# Microcontroller_and_Memory.net
KiCad netlist of a schematic drawn in Altium Designer
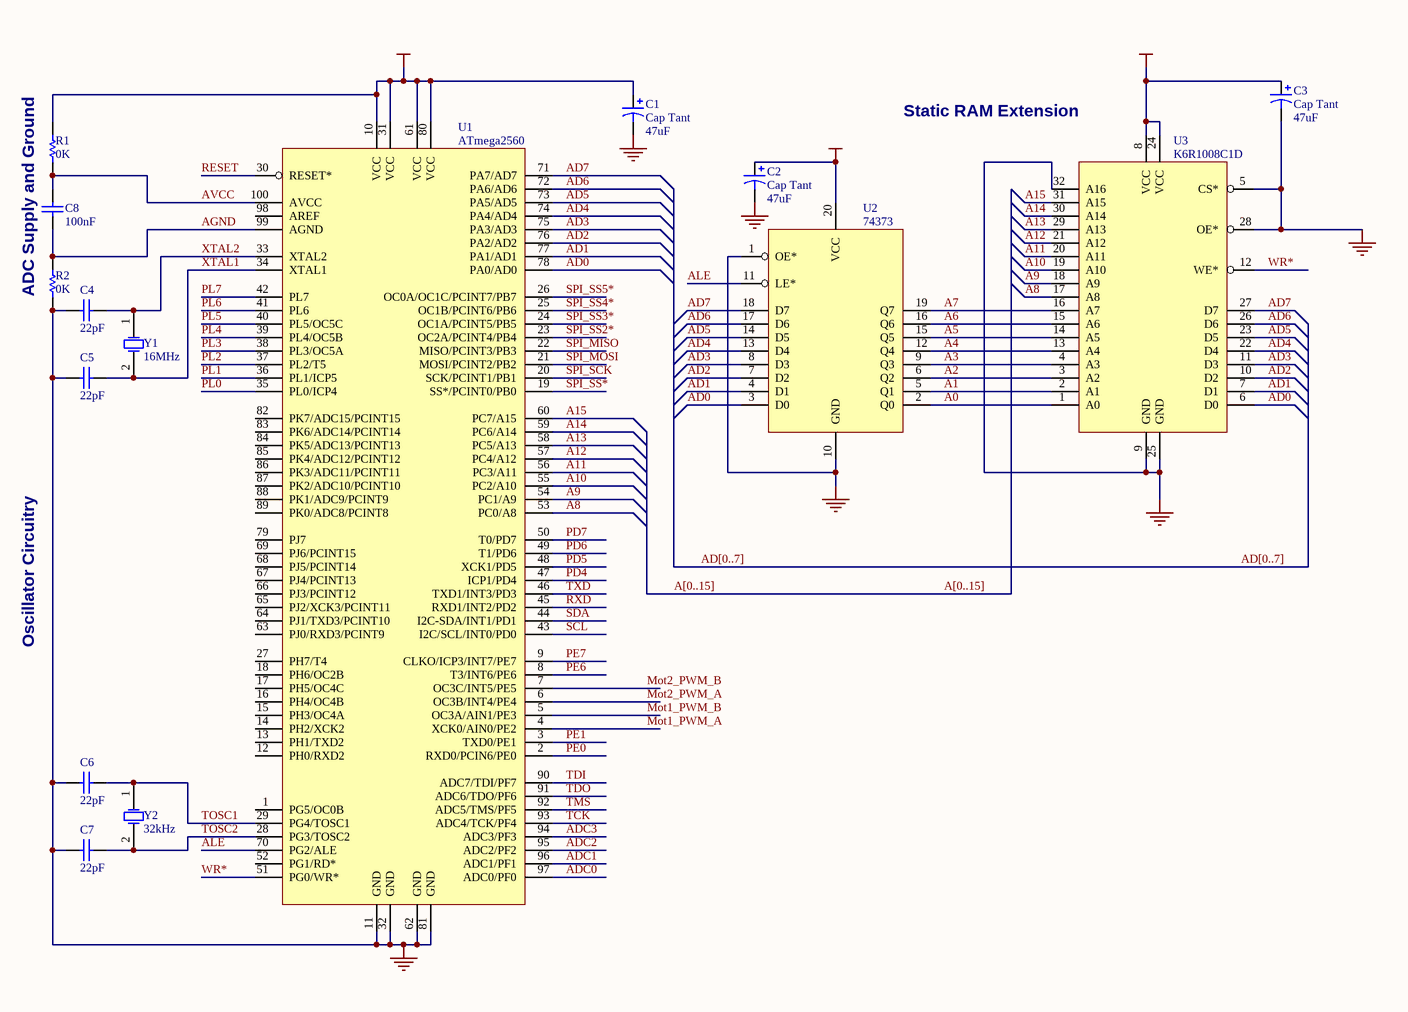
[diagram p0: Microcontroller and Memory.SCHDOC]

(export (version "E")
  (design (tool "Eeschema 10.0.6"))
  (components
    (comp (ref "C1")
      (value "Cap Tant")
      (footprint "CAPR5-4X5")
      (description "Polarized Capacitor (Axial)")
      (fields (field (name "ALTIUM_VALUE") "47uF") (field (name "PUBLISHER") "Altium Limited"))
      (libsource (lib "Miscellaneous Devices") (part "Cap Pol2"))
    )
    (comp (ref "C2")
      (value "Cap Tant")
      (footprint "CAPR5-4X5")
      (description "Polarized Capacitor (Axial)")
      (fields (field (name "ALTIUM_VALUE") "47uF") (field (name "PUBLISHER") "Altium Limited"))
      (libsource (lib "Miscellaneous Devices") (part "Cap Pol2"))
    )
    (comp (ref "C3")
      (value "Cap Tant")
      (footprint "CAPR5-4X5")
      (description "Polarized Capacitor (Axial)")
      (fields (field (name "ALTIUM_VALUE") "47uF") (field (name "PUBLISHER") "Altium Limited"))
      (libsource (lib "Miscellaneous Devices") (part "Cap Pol2"))
    )
    (comp (ref "C4")
      (value "22pF")
      (footprint "BCY-W2/D3.1")
      (description "Capacitor")
      (fields (field (name "PUBLISHER") "Altium Limited"))
      (libsource (lib "Miscellaneous Devices") (part "Cap"))
    )
    (comp (ref "C5")
      (value "22pF")
      (footprint "BCY-W2/D3.1")
      (description "Capacitor")
      (fields (field (name "PUBLISHER") "Altium Limited"))
      (libsource (lib "Miscellaneous Devices") (part "Cap"))
    )
    (comp (ref "C6")
      (value "22pF")
      (footprint "BCY-W2/D3.1")
      (description "Capacitor")
      (fields (field (name "PUBLISHER") "Altium Limited"))
      (libsource (lib "Miscellaneous Devices") (part "Cap"))
    )
    (comp (ref "C7")
      (value "22pF")
      (footprint "BCY-W2/D3.1")
      (description "Capacitor")
      (fields (field (name "PUBLISHER") "Altium Limited"))
      (libsource (lib "Miscellaneous Devices") (part "Cap"))
    )
    (comp (ref "C8")
      (value "100nF")
      (footprint "BCY-W2/D3.1")
      (description "Capacitor")
      (fields (field (name "PUBLISHER") "Altium Limited"))
      (libsource (lib "Miscellaneous Devices") (part "Cap"))
    )
    (comp (ref "R1")
      (value "0K")
      (footprint "AXIAL-0.3")
      (description "Resistor")
      (fields (field (name "PUBLISHER") "Altium Limited"))
      (libsource (lib "Miscellaneous Devices") (part "Res1"))
    )
    (comp (ref "R2")
      (value "0K")
      (footprint "AXIAL-0.3")
      (description "Resistor")
      (fields (field (name "PUBLISHER") "Altium Limited"))
      (libsource (lib "Miscellaneous Devices") (part "Res1"))
    )
    (comp (ref "U1")
      (value "ATmega2560")
      (footprint "Sumo:F-QFP14X14-G100/Z17N")
      (description "Atmel ATmega2560 MCU")
      (libsource (lib "Schematic Library") (part "ATmega2560"))
    )
    (comp (ref "U2")
      (value "74373")
      (footprint "SO-G20/Y1.45")
      (description "Octal 8-bit D-type Latch")
      (libsource (lib "Schematic Library") (part "74373"))
    )
    (comp (ref "U3")
      (value "K6R1008C1D")
      (footprint "SO-G32/Y1.45")
      (description "Samsung 128Kx8 High-Speed Static RAM")
      (libsource (lib "Schematic Library") (part "K6R1008C1D"))
    )
    (comp (ref "Y1")
      (value "16MHz")
      (footprint "BCY-W2/D3.1")
      (description "Crystal Oscillator")
      (fields (field (name "PUBLISHER") "Altium Limited"))
      (libsource (lib "Miscellaneous Devices") (part "XTAL"))
    )
    (comp (ref "Y2")
      (value "32kHz")
      (footprint "BCY-W2/D3.1")
      (description "Crystal Oscillator")
      (fields (field (name "PUBLISHER") "Altium Limited"))
      (libsource (lib "Miscellaneous Devices") (part "XTAL"))
    )
  )
  (nets
    (net (code "1") (name "/A0") (class "Default")
      (node (ref "U2") (pin "2") (pinfunction "Q0_2") (pintype "passive"))
      (node (ref "U3") (pin "1") (pinfunction "A0_1") (pintype "passive"))
    )
    (net (code "2") (name "/A1") (class "Default")
      (node (ref "U2") (pin "5") (pinfunction "Q1_5") (pintype "passive"))
      (node (ref "U3") (pin "2") (pinfunction "A1_2") (pintype "passive"))
    )
    (net (code "3") (name "/A2") (class "Default")
      (node (ref "U2") (pin "6") (pinfunction "Q2_6") (pintype "passive"))
      (node (ref "U3") (pin "3") (pinfunction "A2_3") (pintype "passive"))
    )
    (net (code "4") (name "/A3") (class "Default")
      (node (ref "U2") (pin "9") (pinfunction "Q3_9") (pintype "passive"))
      (node (ref "U3") (pin "4") (pinfunction "A3_4") (pintype "passive"))
    )
    (net (code "5") (name "/A4") (class "Default")
      (node (ref "U2") (pin "12") (pinfunction "Q4_12") (pintype "passive"))
      (node (ref "U3") (pin "13") (pinfunction "A4_13") (pintype "passive"))
    )
    (net (code "6") (name "/A5") (class "Default")
      (node (ref "U2") (pin "15") (pinfunction "Q5_15") (pintype "passive"))
      (node (ref "U3") (pin "14") (pinfunction "A5_14") (pintype "passive"))
    )
    (net (code "7") (name "/A6") (class "Default")
      (node (ref "U2") (pin "16") (pinfunction "Q6_16") (pintype "passive"))
      (node (ref "U3") (pin "15") (pinfunction "A6_15") (pintype "passive"))
    )
    (net (code "8") (name "/A7") (class "Default")
      (node (ref "U2") (pin "19") (pinfunction "Q7_19") (pintype "passive"))
      (node (ref "U3") (pin "16") (pinfunction "A7_16") (pintype "passive"))
    )
    (net (code "9") (name "/A8") (class "Default")
      (node (ref "U1") (pin "53") (pinfunction "PC0/A8_53") (pintype "passive"))
      (node (ref "U3") (pin "17") (pinfunction "A8_17") (pintype "passive"))
    )
    (net (code "10") (name "/A9") (class "Default")
      (node (ref "U1") (pin "54") (pinfunction "PC1/A9_54") (pintype "passive"))
      (node (ref "U3") (pin "18") (pinfunction "A9_18") (pintype "passive"))
    )
    (net (code "11") (name "/A10") (class "Default")
      (node (ref "U1") (pin "55") (pinfunction "PC2/A10_55") (pintype "passive"))
      (node (ref "U3") (pin "19") (pinfunction "A10_19") (pintype "passive"))
    )
    (net (code "12") (name "/A11") (class "Default")
      (node (ref "U1") (pin "56") (pinfunction "PC3/A11_56") (pintype "passive"))
      (node (ref "U3") (pin "20") (pinfunction "A11_20") (pintype "passive"))
    )
    (net (code "13") (name "/A12") (class "Default")
      (node (ref "U1") (pin "57") (pinfunction "PC4/A12_57") (pintype "passive"))
      (node (ref "U3") (pin "21") (pinfunction "A12_21") (pintype "passive"))
    )
    (net (code "14") (name "/A13") (class "Default")
      (node (ref "U1") (pin "58") (pinfunction "PC5/A13_58") (pintype "passive"))
      (node (ref "U3") (pin "29") (pinfunction "A13_29") (pintype "passive"))
    )
    (net (code "15") (name "/A14") (class "Default")
      (node (ref "U1") (pin "59") (pinfunction "PC6/A14_59") (pintype "passive"))
      (node (ref "U3") (pin "30") (pinfunction "A14_30") (pintype "passive"))
    )
    (net (code "16") (name "/A15") (class "Default")
      (node (ref "U1") (pin "60") (pinfunction "PC7/A15_60") (pintype "passive"))
      (node (ref "U3") (pin "31") (pinfunction "A15_31") (pintype "passive"))
    )
    (net (code "17") (name "/AD0") (class "Default")
      (node (ref "U1") (pin "78") (pinfunction "PA0/AD0_78") (pintype "passive"))
      (node (ref "U2") (pin "3") (pinfunction "D0_3") (pintype "passive"))
      (node (ref "U3") (pin "6") (pinfunction "D0_6") (pintype "passive"))
    )
    (net (code "18") (name "/AD1") (class "Default")
      (node (ref "U1") (pin "77") (pinfunction "PA1/AD1_77") (pintype "passive"))
      (node (ref "U2") (pin "4") (pinfunction "D1_4") (pintype "passive"))
      (node (ref "U3") (pin "7") (pinfunction "D1_7") (pintype "passive"))
    )
    (net (code "19") (name "/AD2") (class "Default")
      (node (ref "U1") (pin "76") (pinfunction "PA2/AD2_76") (pintype "passive"))
      (node (ref "U2") (pin "7") (pinfunction "D2_7") (pintype "passive"))
      (node (ref "U3") (pin "10") (pinfunction "D2_10") (pintype "passive"))
    )
    (net (code "20") (name "/AD3") (class "Default")
      (node (ref "U1") (pin "75") (pinfunction "PA3/AD3_75") (pintype "passive"))
      (node (ref "U2") (pin "8") (pinfunction "D3_8") (pintype "passive"))
      (node (ref "U3") (pin "11") (pinfunction "D3_11") (pintype "passive"))
    )
    (net (code "21") (name "/AD4") (class "Default")
      (node (ref "U1") (pin "74") (pinfunction "PA4/AD4_74") (pintype "passive"))
      (node (ref "U2") (pin "13") (pinfunction "D4_13") (pintype "passive"))
      (node (ref "U3") (pin "22") (pinfunction "D4_22") (pintype "passive"))
    )
    (net (code "22") (name "/AD5") (class "Default")
      (node (ref "U1") (pin "73") (pinfunction "PA5/AD5_73") (pintype "passive"))
      (node (ref "U2") (pin "14") (pinfunction "D5_14") (pintype "passive"))
      (node (ref "U3") (pin "23") (pinfunction "D5_23") (pintype "passive"))
    )
    (net (code "23") (name "/AD6") (class "Default")
      (node (ref "U1") (pin "72") (pinfunction "PA6/AD6_72") (pintype "passive"))
      (node (ref "U2") (pin "17") (pinfunction "D6_17") (pintype "passive"))
      (node (ref "U3") (pin "26") (pinfunction "D6_26") (pintype "passive"))
    )
    (net (code "24") (name "/AD7") (class "Default")
      (node (ref "U1") (pin "71") (pinfunction "PA7/AD7_71") (pintype "passive"))
      (node (ref "U2") (pin "18") (pinfunction "D7_18") (pintype "passive"))
      (node (ref "U3") (pin "27") (pinfunction "D7_27") (pintype "passive"))
    )
    (net (code "25") (name "/ADC0") (class "Default")
      (node (ref "U1") (pin "97") (pinfunction "ADC0/PF0_97") (pintype "passive"))
    )
    (net (code "26") (name "/ADC1") (class "Default")
      (node (ref "U1") (pin "96") (pinfunction "ADC1/PF1_96") (pintype "passive"))
    )
    (net (code "27") (name "/ADC2") (class "Default")
      (node (ref "U1") (pin "95") (pinfunction "ADC2/PF2_95") (pintype "passive"))
    )
    (net (code "28") (name "/ADC3") (class "Default")
      (node (ref "U1") (pin "94") (pinfunction "ADC3/PF3_94") (pintype "passive"))
    )
    (net (code "30") (name "/AGND") (class "Default")
      (node (ref "C8") (pin "2") (pinfunction "2_2") (pintype "passive"))
      (node (ref "R2") (pin "2") (pinfunction "2_2") (pintype "passive"))
      (node (ref "U1") (pin "99") (pinfunction "AGND_99") (pintype "passive"))
    )
    (net (code "31") (name "/ALE") (class "Default")
      (node (ref "U1") (pin "70") (pinfunction "PG2/ALE_70") (pintype "passive"))
      (node (ref "U2") (pin "11") (pinfunction "LE*_11") (pintype "passive"))
    )
    (net (code "32") (name "/AVCC") (class "Default")
      (node (ref "C8") (pin "1") (pinfunction "1_1") (pintype "passive"))
      (node (ref "R1") (pin "1") (pinfunction "1_1") (pintype "passive"))
      (node (ref "U1") (pin "100") (pinfunction "AVCC_100") (pintype "passive"))
    )
    (net (code "34") (name "/Mot1_PWM_A") (class "Default")
      (node (ref "U1") (pin "4") (pinfunction "XCK0/AIN0/PE2_4") (pintype "passive"))
    )
    (net (code "35") (name "/Mot1_PWM_B") (class "Default")
      (node (ref "U1") (pin "5") (pinfunction "OC3A/AIN1/PE3_5") (pintype "passive"))
    )
    (net (code "36") (name "/Mot2_PWM_A") (class "Default")
      (node (ref "U1") (pin "6") (pinfunction "OC3B/INT4/PE4_6") (pintype "passive"))
    )
    (net (code "37") (name "/Mot2_PWM_B") (class "Default")
      (node (ref "U1") (pin "7") (pinfunction "OC3C/INT5/PE5_7") (pintype "passive"))
    )
    (net (code "38") (name "/PD4") (class "Default")
      (node (ref "U1") (pin "47") (pinfunction "ICP1/PD4_47") (pintype "passive"))
    )
    (net (code "39") (name "/PD5") (class "Default")
      (node (ref "U1") (pin "48") (pinfunction "XCK1/PD5_48") (pintype "passive"))
    )
    (net (code "40") (name "/PD6") (class "Default")
      (node (ref "U1") (pin "49") (pinfunction "T1/PD6_49") (pintype "passive"))
    )
    (net (code "41") (name "/PD7") (class "Default")
      (node (ref "U1") (pin "50") (pinfunction "T0/PD7_50") (pintype "passive"))
    )
    (net (code "42") (name "/PE0") (class "Default")
      (node (ref "U1") (pin "2") (pinfunction "RXD0/PCIN6/PE0_2") (pintype "passive"))
    )
    (net (code "43") (name "/PE1") (class "Default")
      (node (ref "U1") (pin "3") (pinfunction "TXD0/PE1_3") (pintype "passive"))
    )
    (net (code "44") (name "/PE6") (class "Default")
      (node (ref "U1") (pin "8") (pinfunction "T3/INT6/PE6_8") (pintype "passive"))
    )
    (net (code "45") (name "/PE7") (class "Default")
      (node (ref "U1") (pin "9") (pinfunction "CLKO/ICP3/INT7/PE7_9") (pintype "passive"))
    )
    (net (code "46") (name "/PL0") (class "Default")
      (node (ref "U1") (pin "35") (pinfunction "PL0/ICP4_35") (pintype "passive"))
    )
    (net (code "47") (name "/PL1") (class "Default")
      (node (ref "U1") (pin "36") (pinfunction "PL1/ICP5_36") (pintype "passive"))
    )
    (net (code "48") (name "/PL2") (class "Default")
      (node (ref "U1") (pin "37") (pinfunction "PL2/T5_37") (pintype "passive"))
    )
    (net (code "49") (name "/PL3") (class "Default")
      (node (ref "U1") (pin "38") (pinfunction "PL3/OC5A_38") (pintype "passive"))
    )
    (net (code "50") (name "/PL4") (class "Default")
      (node (ref "U1") (pin "39") (pinfunction "PL4/OC5B_39") (pintype "passive"))
    )
    (net (code "51") (name "/PL5") (class "Default")
      (node (ref "U1") (pin "40") (pinfunction "PL5/OC5C_40") (pintype "passive"))
    )
    (net (code "52") (name "/PL6") (class "Default")
      (node (ref "U1") (pin "41") (pinfunction "PL6_41") (pintype "passive"))
    )
    (net (code "53") (name "/PL7") (class "Default")
      (node (ref "U1") (pin "42") (pinfunction "PL7_42") (pintype "passive"))
    )
    (net (code "54") (name "/RESET") (class "Default")
      (node (ref "U1") (pin "30") (pinfunction "RESET*_30") (pintype "passive"))
    )
    (net (code "55") (name "/RXD") (class "Default")
      (node (ref "U1") (pin "45") (pinfunction "RXD1/INT2/PD2_45") (pintype "passive"))
    )
    (net (code "56") (name "/SCL") (class "Default")
      (node (ref "U1") (pin "43") (pinfunction "I2C/SCL/INT0/PD0_43") (pintype "passive"))
    )
    (net (code "57") (name "/SDA") (class "Default")
      (node (ref "U1") (pin "44") (pinfunction "I2C-SDA/INT1/PD1_44") (pintype "passive"))
    )
    (net (code "58") (name "/SPI_MISO") (class "Default")
      (node (ref "U1") (pin "22") (pinfunction "MISO/PCINT3/PB3_22") (pintype "passive"))
    )
    (net (code "59") (name "/SPI_MOSI") (class "Default")
      (node (ref "U1") (pin "21") (pinfunction "MOSI/PCINT2/PB2_21") (pintype "passive"))
    )
    (net (code "60") (name "/SPI_SCK") (class "Default")
      (node (ref "U1") (pin "20") (pinfunction "SCK/PCINT1/PB1_20") (pintype "passive"))
    )
    (net (code "61") (name "/SPI_SS*") (class "Default")
      (node (ref "U1") (pin "19") (pinfunction "SS*/PCINT0/PB0_19") (pintype "passive"))
    )
    (net (code "62") (name "/SPI_SS2*") (class "Default")
      (node (ref "U1") (pin "23") (pinfunction "OC2A/PCINT4/PB4_23") (pintype "passive"))
    )
    (net (code "63") (name "/SPI_SS3*") (class "Default")
      (node (ref "U1") (pin "24") (pinfunction "OC1A/PCINT5/PB5_24") (pintype "passive"))
    )
    (net (code "64") (name "/SPI_SS4*") (class "Default")
      (node (ref "U1") (pin "25") (pinfunction "OC1B/PCINT6/PB6_25") (pintype "passive"))
    )
    (net (code "65") (name "/SPI_SS5*") (class "Default")
      (node (ref "U1") (pin "26") (pinfunction "OC0A/OC1C/PCINT7/PB7_26") (pintype "passive"))
    )
    (net (code "66") (name "/TCK") (class "Default")
      (node (ref "U1") (pin "93") (pinfunction "ADC4/TCK/PF4_93") (pintype "passive"))
    )
    (net (code "67") (name "/TDI") (class "Default")
      (node (ref "U1") (pin "90") (pinfunction "ADC7/TDI/PF7_90") (pintype "passive"))
    )
    (net (code "68") (name "/TDO") (class "Default")
      (node (ref "U1") (pin "91") (pinfunction "ADC6/TDO/PF6_91") (pintype "passive"))
    )
    (net (code "69") (name "/TMS") (class "Default")
      (node (ref "U1") (pin "92") (pinfunction "ADC5/TMS/PF5_92") (pintype "passive"))
    )
    (net (code "70") (name "/TOSC1") (class "Default")
      (node (ref "C6") (pin "2") (pinfunction "2_2") (pintype "passive"))
      (node (ref "U1") (pin "29") (pinfunction "PG4/TOSC1_29") (pintype "passive"))
      (node (ref "Y2") (pin "1") (pinfunction "OSC1_1") (pintype "passive"))
    )
    (net (code "71") (name "/TOSC2") (class "Default")
      (node (ref "C7") (pin "2") (pinfunction "2_2") (pintype "passive"))
      (node (ref "U1") (pin "28") (pinfunction "PG3/TOSC2_28") (pintype "passive"))
      (node (ref "Y2") (pin "2") (pinfunction "OSC2_2") (pintype "passive"))
    )
    (net (code "72") (name "/TXD") (class "Default")
      (node (ref "U1") (pin "46") (pinfunction "TXD1/INT3/PD3_46") (pintype "passive"))
    )
    (net (code "73") (name "/WR*") (class "Default")
      (node (ref "U1") (pin "51") (pinfunction "PG0/WR*_51") (pintype "passive"))
      (node (ref "U3") (pin "12") (pinfunction "WE*_12") (pintype "passive"))
    )
    (net (code "74") (name "/XTAL1") (class "Default")
      (node (ref "C5") (pin "2") (pinfunction "2_2") (pintype "passive"))
      (node (ref "U1") (pin "34") (pinfunction "XTAL1_34") (pintype "passive"))
      (node (ref "Y1") (pin "2") (pinfunction "OSC2_2") (pintype "passive"))
    )
    (net (code "75") (name "/XTAL2") (class "Default")
      (node (ref "C4") (pin "2") (pinfunction "2_2") (pintype "passive"))
      (node (ref "U1") (pin "33") (pinfunction "XTAL2_33") (pintype "passive"))
      (node (ref "Y1") (pin "1") (pinfunction "OSC1_1") (pintype "passive"))
    )
    (net (code "76") (name "5V") (class "Default")
      (node (ref "C1") (pin "1") (pinfunction "1_1") (pintype "passive"))
      (node (ref "C2") (pin "1") (pinfunction "1_1") (pintype "passive"))
      (node (ref "C3") (pin "1") (pinfunction "1_1") (pintype "passive"))
      (node (ref "R1") (pin "2") (pinfunction "2_2") (pintype "passive"))
      (node (ref "U1") (pin "10") (pinfunction "VCC_10") (pintype "passive"))
      (node (ref "U1") (pin "31") (pinfunction "VCC_31") (pintype "passive"))
      (node (ref "U1") (pin "61") (pinfunction "VCC_61") (pintype "passive"))
      (node (ref "U1") (pin "80") (pinfunction "VCC_80") (pintype "passive"))
      (node (ref "U2") (pin "20") (pinfunction "VCC_20") (pintype "passive"))
      (node (ref "U3") (pin "24") (pinfunction "VCC_24") (pintype "passive"))
      (node (ref "U3") (pin "8") (pinfunction "VCC_8") (pintype "passive"))
    )
    (net (code "77") (name "GND") (class "Default")
      (node (ref "C1") (pin "2") (pinfunction "2_2") (pintype "passive"))
      (node (ref "C2") (pin "2") (pinfunction "2_2") (pintype "passive"))
      (node (ref "C3") (pin "2") (pinfunction "2_2") (pintype "passive"))
      (node (ref "C4") (pin "1") (pinfunction "1_1") (pintype "passive"))
      (node (ref "C5") (pin "1") (pinfunction "1_1") (pintype "passive"))
      (node (ref "C6") (pin "1") (pinfunction "1_1") (pintype "passive"))
      (node (ref "C7") (pin "1") (pinfunction "1_1") (pintype "passive"))
      (node (ref "R2") (pin "1") (pinfunction "1_1") (pintype "passive"))
      (node (ref "U1") (pin "11") (pinfunction "GND_11") (pintype "passive"))
      (node (ref "U1") (pin "32") (pinfunction "GND_32") (pintype "passive"))
      (node (ref "U1") (pin "62") (pinfunction "GND_62") (pintype "passive"))
      (node (ref "U1") (pin "81") (pinfunction "GND_81") (pintype "passive"))
      (node (ref "U2") (pin "1") (pinfunction "OE*_1") (pintype "passive"))
      (node (ref "U2") (pin "10") (pinfunction "GND_10") (pintype "passive"))
      (node (ref "U3") (pin "25") (pinfunction "GND_25") (pintype "passive"))
      (node (ref "U3") (pin "28") (pinfunction "OE*_28") (pintype "passive"))
      (node (ref "U3") (pin "32") (pinfunction "A16_32") (pintype "passive"))
      (node (ref "U3") (pin "5") (pinfunction "CS*_5") (pintype "passive"))
      (node (ref "U3") (pin "9") (pinfunction "GND_9") (pintype "passive"))
    )
    (net (code "78") (name "unconnected-(U1-AREF-Pad98)") (class "Default")
      (node (ref "U1") (pin "98") (pinfunction "AREF_98") (pintype "passive"))
    )
    (net (code "79") (name "unconnected-(U1-PG1{slash}RD*-Pad52)") (class "Default")
      (node (ref "U1") (pin "52") (pinfunction "PG1/RD*_52") (pintype "passive"))
    )
    (net (code "80") (name "unconnected-(U1-PG5{slash}OC0B-Pad1)") (class "Default")
      (node (ref "U1") (pin "1") (pinfunction "PG5/OC0B_1") (pintype "passive"))
    )
    (net (code "81") (name "unconnected-(U1-PH0{slash}RXD2-Pad12)") (class "Default")
      (node (ref "U1") (pin "12") (pinfunction "PH0/RXD2_12") (pintype "passive"))
    )
    (net (code "82") (name "unconnected-(U1-PH1{slash}TXD2-Pad13)") (class "Default")
      (node (ref "U1") (pin "13") (pinfunction "PH1/TXD2_13") (pintype "passive"))
    )
    (net (code "83") (name "unconnected-(U1-PH2{slash}XCK2-Pad14)") (class "Default")
      (node (ref "U1") (pin "14") (pinfunction "PH2/XCK2_14") (pintype "passive"))
    )
    (net (code "84") (name "unconnected-(U1-PH3{slash}OC4A-Pad15)") (class "Default")
      (node (ref "U1") (pin "15") (pinfunction "PH3/OC4A_15") (pintype "passive"))
    )
    (net (code "85") (name "unconnected-(U1-PH4{slash}OC4B-Pad16)") (class "Default")
      (node (ref "U1") (pin "16") (pinfunction "PH4/OC4B_16") (pintype "passive"))
    )
    (net (code "86") (name "unconnected-(U1-PH5{slash}OC4C-Pad17)") (class "Default")
      (node (ref "U1") (pin "17") (pinfunction "PH5/OC4C_17") (pintype "passive"))
    )
    (net (code "87") (name "unconnected-(U1-PH6{slash}OC2B-Pad18)") (class "Default")
      (node (ref "U1") (pin "18") (pinfunction "PH6/OC2B_18") (pintype "passive"))
    )
    (net (code "88") (name "unconnected-(U1-PH7{slash}T4-Pad27)") (class "Default")
      (node (ref "U1") (pin "27") (pinfunction "PH7/T4_27") (pintype "passive"))
    )
    (net (code "89") (name "unconnected-(U1-PJ0{slash}RXD3{slash}PCINT9-Pad63)") (class "Default")
      (node (ref "U1") (pin "63") (pinfunction "PJ0/RXD3/PCINT9_63") (pintype "passive"))
    )
    (net (code "90") (name "unconnected-(U1-PJ1{slash}TXD3{slash}PCINT10-Pad64)") (class "Default")
      (node (ref "U1") (pin "64") (pinfunction "PJ1/TXD3/PCINT10_64") (pintype "passive"))
    )
    (net (code "91") (name "unconnected-(U1-PJ2{slash}XCK3{slash}PCINT11-Pad65)") (class "Default")
      (node (ref "U1") (pin "65") (pinfunction "PJ2/XCK3/PCINT11_65") (pintype "passive"))
    )
    (net (code "92") (name "unconnected-(U1-PJ3{slash}PCINT12-Pad66)") (class "Default")
      (node (ref "U1") (pin "66") (pinfunction "PJ3/PCINT12_66") (pintype "passive"))
    )
    (net (code "93") (name "unconnected-(U1-PJ4{slash}PCINT13-Pad67)") (class "Default")
      (node (ref "U1") (pin "67") (pinfunction "PJ4/PCINT13_67") (pintype "passive"))
    )
    (net (code "94") (name "unconnected-(U1-PJ5{slash}PCINT14-Pad68)") (class "Default")
      (node (ref "U1") (pin "68") (pinfunction "PJ5/PCINT14_68") (pintype "passive"))
    )
    (net (code "95") (name "unconnected-(U1-PJ6{slash}PCINT15-Pad69)") (class "Default")
      (node (ref "U1") (pin "69") (pinfunction "PJ6/PCINT15_69") (pintype "passive"))
    )
    (net (code "96") (name "unconnected-(U1-PJ7-Pad79)") (class "Default")
      (node (ref "U1") (pin "79") (pinfunction "PJ7_79") (pintype "passive"))
    )
    (net (code "97") (name "unconnected-(U1-PK0{slash}ADC8{slash}PCINT8-Pad89)") (class "Default")
      (node (ref "U1") (pin "89") (pinfunction "PK0/ADC8/PCINT8_89") (pintype "passive"))
    )
    (net (code "98") (name "unconnected-(U1-PK1{slash}ADC9{slash}PCINT9-Pad88)") (class "Default")
      (node (ref "U1") (pin "88") (pinfunction "PK1/ADC9/PCINT9_88") (pintype "passive"))
    )
    (net (code "99") (name "unconnected-(U1-PK2{slash}ADC10{slash}PCINT10-Pad87)") (class "Default")
      (node (ref "U1") (pin "87") (pinfunction "PK2/ADC10/PCINT10_87") (pintype "passive"))
    )
    (net (code "100") (name "unconnected-(U1-PK3{slash}ADC11{slash}PCINT11-Pad86)") (class "Default")
      (node (ref "U1") (pin "86") (pinfunction "PK3/ADC11/PCINT11_86") (pintype "passive"))
    )
    (net (code "101") (name "unconnected-(U1-PK4{slash}ADC12{slash}PCINT12-Pad85)") (class "Default")
      (node (ref "U1") (pin "85") (pinfunction "PK4/ADC12/PCINT12_85") (pintype "passive"))
    )
    (net (code "102") (name "unconnected-(U1-PK5{slash}ADC13{slash}PCINT13-Pad84)") (class "Default")
      (node (ref "U1") (pin "84") (pinfunction "PK5/ADC13/PCINT13_84") (pintype "passive"))
    )
    (net (code "103") (name "unconnected-(U1-PK6{slash}ADC14{slash}PCINT14-Pad83)") (class "Default")
      (node (ref "U1") (pin "83") (pinfunction "PK6/ADC14/PCINT14_83") (pintype "passive"))
    )
    (net (code "104") (name "unconnected-(U1-PK7{slash}ADC15{slash}PCINT15-Pad82)") (class "Default")
      (node (ref "U1") (pin "82") (pinfunction "PK7/ADC15/PCINT15_82") (pintype "passive"))
    )
  )
)
